# ONOFRE_DEV_SHIELD_3_0.net
KiCad netlist of a schematic drawn in EAGLE
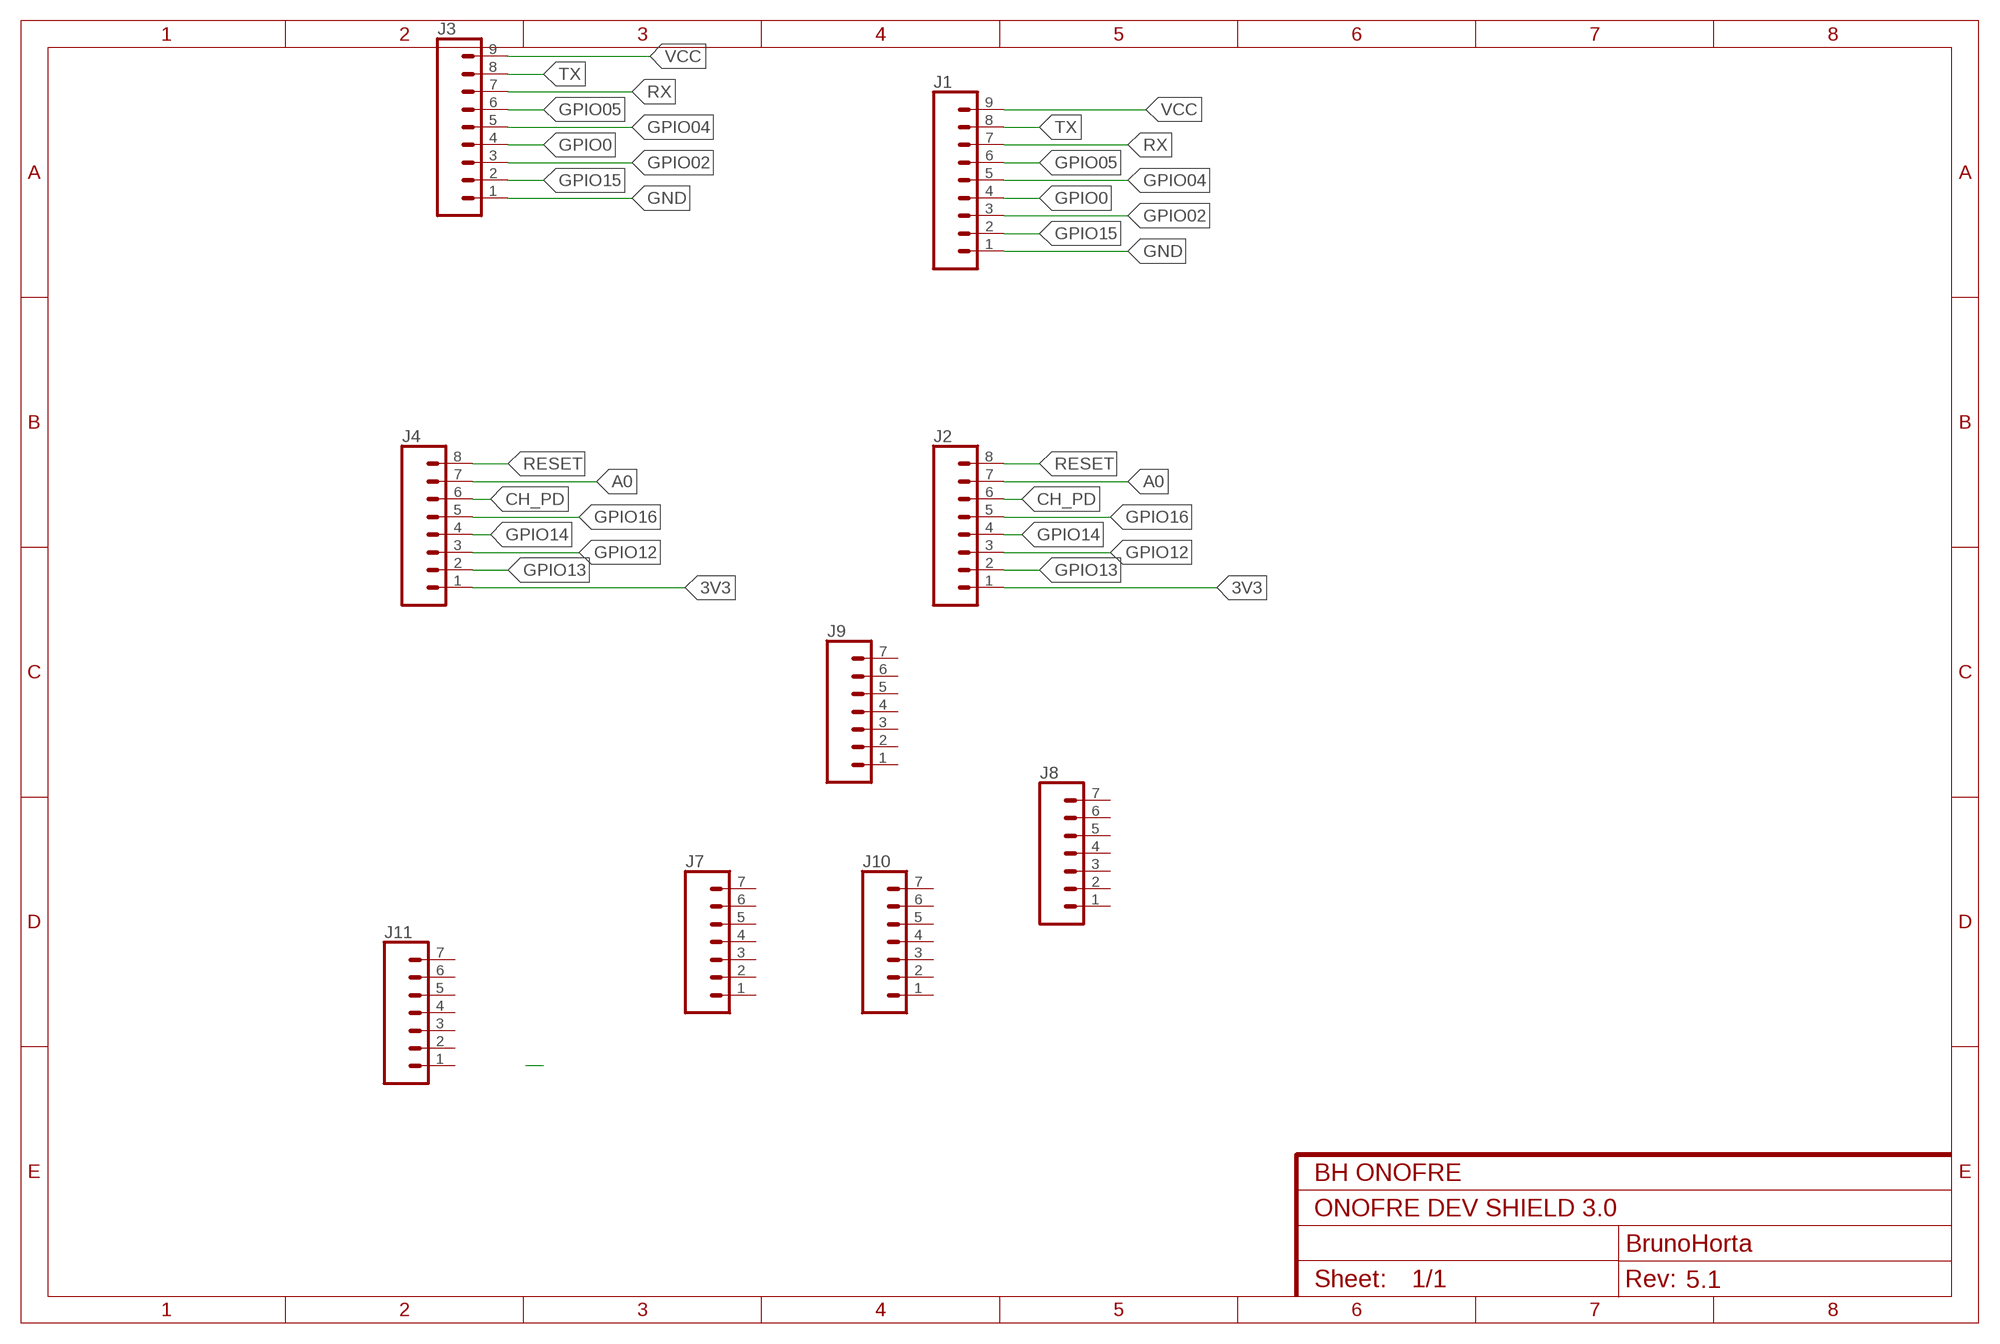
[diagram p0: schematic, sheet 1]

(export (version "E")
  (design (tool "Eeschema 10.0.6"))
  (components
    (comp (ref "J1")
      (value "CONN_09")
      (footprint "eagle-import:1X09")
      (libsource (lib "eagle-import") (part "CONN_09"))
    )
    (comp (ref "J2")
      (value "CONN_08\"")
      (footprint "eagle-import:1X08")
      (libsource (lib "eagle-import") (part "CONN_08{dblquote}"))
    )
    (comp (ref "J3")
      (value "CONN_09")
      (footprint "eagle-import:1X09")
      (libsource (lib "eagle-import") (part "CONN_09"))
    )
    (comp (ref "J4")
      (value "CONN_08\"")
      (footprint "eagle-import:1X08")
      (libsource (lib "eagle-import") (part "CONN_08{dblquote}"))
    )
    (comp (ref "J7")
      (value "CONN_07NO_SILK")
      (footprint "eagle-import:1X07_NO_SILK")
      (libsource (lib "eagle-import") (part "CONN_07NO_SILK"))
    )
    (comp (ref "J8")
      (value "CONN_07NO_SILK")
      (footprint "eagle-import:1X07_NO_SILK")
      (libsource (lib "eagle-import") (part "CONN_07NO_SILK"))
    )
    (comp (ref "J9")
      (value "CONN_07NO_SILK")
      (footprint "eagle-import:1X07_NO_SILK")
      (libsource (lib "eagle-import") (part "CONN_07NO_SILK"))
    )
    (comp (ref "J10")
      (value "CONN_07NO_SILK")
      (footprint "eagle-import:1X07_NO_SILK")
      (libsource (lib "eagle-import") (part "CONN_07NO_SILK"))
    )
    (comp (ref "J11")
      (value "CONN_07NO_SILK")
      (footprint "eagle-import:1X07_NO_SILK")
      (libsource (lib "eagle-import") (part "CONN_07NO_SILK"))
    )
  )
  (nets
    (net (code "1") (name "3V3") (class "Default")
      (node (ref "J2") (pin "1") (pinfunction "1_1") (pintype "passive"))
      (node (ref "J4") (pin "1") (pinfunction "1_1") (pintype "passive"))
    )
    (net (code "2") (name "A0") (class "Default")
      (node (ref "J2") (pin "7") (pinfunction "7_7") (pintype "passive"))
      (node (ref "J4") (pin "7") (pinfunction "7_7") (pintype "passive"))
    )
    (net (code "3") (name "CH_PD") (class "Default")
      (node (ref "J2") (pin "6") (pinfunction "6_6") (pintype "passive"))
      (node (ref "J4") (pin "6") (pinfunction "6_6") (pintype "passive"))
    )
    (net (code "4") (name "GND") (class "Default")
      (node (ref "J1") (pin "1") (pinfunction "1_1") (pintype "passive"))
      (node (ref "J3") (pin "1") (pinfunction "1_1") (pintype "passive"))
    )
    (net (code "5") (name "GPIO0") (class "Default")
      (node (ref "J1") (pin "4") (pinfunction "4_4") (pintype "passive"))
      (node (ref "J3") (pin "4") (pinfunction "4_4") (pintype "passive"))
    )
    (net (code "6") (name "GPIO02") (class "Default")
      (node (ref "J1") (pin "3") (pinfunction "3_3") (pintype "passive"))
      (node (ref "J3") (pin "3") (pinfunction "3_3") (pintype "passive"))
    )
    (net (code "7") (name "GPIO04") (class "Default")
      (node (ref "J1") (pin "5") (pinfunction "5_5") (pintype "passive"))
      (node (ref "J3") (pin "5") (pinfunction "5_5") (pintype "passive"))
    )
    (net (code "8") (name "GPIO05") (class "Default")
      (node (ref "J1") (pin "6") (pinfunction "6_6") (pintype "passive"))
      (node (ref "J3") (pin "6") (pinfunction "6_6") (pintype "passive"))
    )
    (net (code "9") (name "GPIO12") (class "Default")
      (node (ref "J2") (pin "3") (pinfunction "3_3") (pintype "passive"))
      (node (ref "J4") (pin "3") (pinfunction "3_3") (pintype "passive"))
    )
    (net (code "10") (name "GPIO13") (class "Default")
      (node (ref "J2") (pin "2") (pinfunction "2_2") (pintype "passive"))
      (node (ref "J4") (pin "2") (pinfunction "2_2") (pintype "passive"))
    )
    (net (code "11") (name "GPIO14") (class "Default")
      (node (ref "J2") (pin "4") (pinfunction "4_4") (pintype "passive"))
      (node (ref "J4") (pin "4") (pinfunction "4_4") (pintype "passive"))
    )
    (net (code "12") (name "GPIO15") (class "Default")
      (node (ref "J1") (pin "2") (pinfunction "2_2") (pintype "passive"))
      (node (ref "J3") (pin "2") (pinfunction "2_2") (pintype "passive"))
    )
    (net (code "13") (name "GPIO16") (class "Default")
      (node (ref "J2") (pin "5") (pinfunction "5_5") (pintype "passive"))
      (node (ref "J4") (pin "5") (pinfunction "5_5") (pintype "passive"))
    )
    (net (code "14") (name "RESET") (class "Default")
      (node (ref "J2") (pin "8") (pinfunction "8_8") (pintype "passive"))
      (node (ref "J4") (pin "8") (pinfunction "8_8") (pintype "passive"))
    )
    (net (code "15") (name "RX") (class "Default")
      (node (ref "J1") (pin "7") (pinfunction "7_7") (pintype "passive"))
      (node (ref "J3") (pin "7") (pinfunction "7_7") (pintype "passive"))
    )
    (net (code "16") (name "TX") (class "Default")
      (node (ref "J1") (pin "8") (pinfunction "8_8") (pintype "passive"))
      (node (ref "J3") (pin "8") (pinfunction "8_8") (pintype "passive"))
    )
    (net (code "17") (name "VCC") (class "Default")
      (node (ref "J1") (pin "9") (pinfunction "9_9") (pintype "passive"))
      (node (ref "J3") (pin "9") (pinfunction "9_9") (pintype "passive"))
    )
    (net (code "18") (name "unconnected-(J7-Pad1)") (class "Default")
      (node (ref "J7") (pin "1") (pinfunction "1_1") (pintype "passive"))
    )
    (net (code "19") (name "unconnected-(J7-Pad2)") (class "Default")
      (node (ref "J7") (pin "2") (pinfunction "2_2") (pintype "passive"))
    )
    (net (code "20") (name "unconnected-(J7-Pad3)") (class "Default")
      (node (ref "J7") (pin "3") (pinfunction "3_3") (pintype "passive"))
    )
    (net (code "21") (name "unconnected-(J7-Pad4)") (class "Default")
      (node (ref "J7") (pin "4") (pinfunction "4_4") (pintype "passive"))
    )
    (net (code "22") (name "unconnected-(J7-Pad5)") (class "Default")
      (node (ref "J7") (pin "5") (pinfunction "5_5") (pintype "passive"))
    )
    (net (code "23") (name "unconnected-(J7-Pad6)") (class "Default")
      (node (ref "J7") (pin "6") (pinfunction "6_6") (pintype "passive"))
    )
    (net (code "24") (name "unconnected-(J7-Pad7)") (class "Default")
      (node (ref "J7") (pin "7") (pinfunction "7_7") (pintype "passive"))
    )
    (net (code "25") (name "unconnected-(J8-Pad1)") (class "Default")
      (node (ref "J8") (pin "1") (pinfunction "1_1") (pintype "passive"))
    )
    (net (code "26") (name "unconnected-(J8-Pad2)") (class "Default")
      (node (ref "J8") (pin "2") (pinfunction "2_2") (pintype "passive"))
    )
    (net (code "27") (name "unconnected-(J8-Pad3)") (class "Default")
      (node (ref "J8") (pin "3") (pinfunction "3_3") (pintype "passive"))
    )
    (net (code "28") (name "unconnected-(J8-Pad4)") (class "Default")
      (node (ref "J8") (pin "4") (pinfunction "4_4") (pintype "passive"))
    )
    (net (code "29") (name "unconnected-(J8-Pad5)") (class "Default")
      (node (ref "J8") (pin "5") (pinfunction "5_5") (pintype "passive"))
    )
    (net (code "30") (name "unconnected-(J8-Pad6)") (class "Default")
      (node (ref "J8") (pin "6") (pinfunction "6_6") (pintype "passive"))
    )
    (net (code "31") (name "unconnected-(J8-Pad7)") (class "Default")
      (node (ref "J8") (pin "7") (pinfunction "7_7") (pintype "passive"))
    )
    (net (code "32") (name "unconnected-(J9-Pad1)") (class "Default")
      (node (ref "J9") (pin "1") (pinfunction "1_1") (pintype "passive"))
    )
    (net (code "33") (name "unconnected-(J9-Pad2)") (class "Default")
      (node (ref "J9") (pin "2") (pinfunction "2_2") (pintype "passive"))
    )
    (net (code "34") (name "unconnected-(J9-Pad3)") (class "Default")
      (node (ref "J9") (pin "3") (pinfunction "3_3") (pintype "passive"))
    )
    (net (code "35") (name "unconnected-(J9-Pad4)") (class "Default")
      (node (ref "J9") (pin "4") (pinfunction "4_4") (pintype "passive"))
    )
    (net (code "36") (name "unconnected-(J9-Pad5)") (class "Default")
      (node (ref "J9") (pin "5") (pinfunction "5_5") (pintype "passive"))
    )
    (net (code "37") (name "unconnected-(J9-Pad6)") (class "Default")
      (node (ref "J9") (pin "6") (pinfunction "6_6") (pintype "passive"))
    )
    (net (code "38") (name "unconnected-(J9-Pad7)") (class "Default")
      (node (ref "J9") (pin "7") (pinfunction "7_7") (pintype "passive"))
    )
    (net (code "39") (name "unconnected-(J10-Pad1)") (class "Default")
      (node (ref "J10") (pin "1") (pinfunction "1_1") (pintype "passive"))
    )
    (net (code "40") (name "unconnected-(J10-Pad2)") (class "Default")
      (node (ref "J10") (pin "2") (pinfunction "2_2") (pintype "passive"))
    )
    (net (code "41") (name "unconnected-(J10-Pad3)") (class "Default")
      (node (ref "J10") (pin "3") (pinfunction "3_3") (pintype "passive"))
    )
    (net (code "42") (name "unconnected-(J10-Pad4)") (class "Default")
      (node (ref "J10") (pin "4") (pinfunction "4_4") (pintype "passive"))
    )
    (net (code "43") (name "unconnected-(J10-Pad5)") (class "Default")
      (node (ref "J10") (pin "5") (pinfunction "5_5") (pintype "passive"))
    )
    (net (code "44") (name "unconnected-(J10-Pad6)") (class "Default")
      (node (ref "J10") (pin "6") (pinfunction "6_6") (pintype "passive"))
    )
    (net (code "45") (name "unconnected-(J10-Pad7)") (class "Default")
      (node (ref "J10") (pin "7") (pinfunction "7_7") (pintype "passive"))
    )
    (net (code "46") (name "unconnected-(J11-Pad1)") (class "Default")
      (node (ref "J11") (pin "1") (pinfunction "1_1") (pintype "passive"))
    )
    (net (code "47") (name "unconnected-(J11-Pad2)") (class "Default")
      (node (ref "J11") (pin "2") (pinfunction "2_2") (pintype "passive"))
    )
    (net (code "48") (name "unconnected-(J11-Pad3)") (class "Default")
      (node (ref "J11") (pin "3") (pinfunction "3_3") (pintype "passive"))
    )
    (net (code "49") (name "unconnected-(J11-Pad4)") (class "Default")
      (node (ref "J11") (pin "4") (pinfunction "4_4") (pintype "passive"))
    )
    (net (code "50") (name "unconnected-(J11-Pad5)") (class "Default")
      (node (ref "J11") (pin "5") (pinfunction "5_5") (pintype "passive"))
    )
    (net (code "51") (name "unconnected-(J11-Pad6)") (class "Default")
      (node (ref "J11") (pin "6") (pinfunction "6_6") (pintype "passive"))
    )
    (net (code "52") (name "unconnected-(J11-Pad7)") (class "Default")
      (node (ref "J11") (pin "7") (pinfunction "7_7") (pintype "passive"))
    )
  )
)
